# Sheet1.net
KiCad netlist of a schematic drawn in Altium Designer
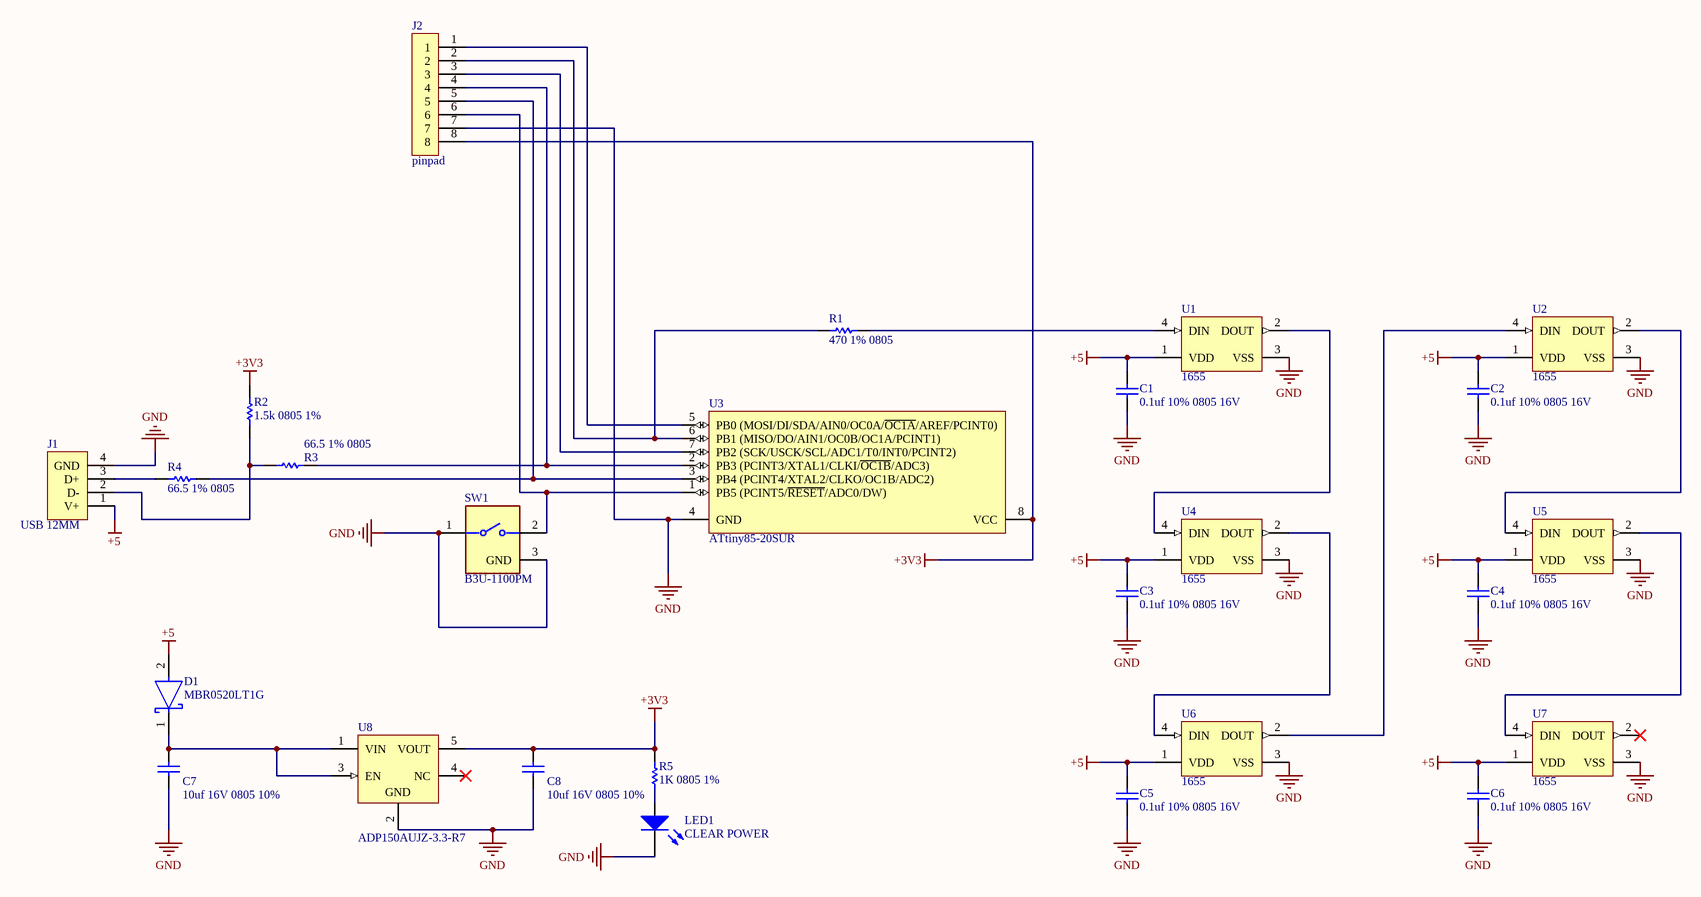
[diagram p0: Sheet1.SchDoc]

(export (version "E")
  (design (tool "Eeschema 10.0.6"))
  (components
    (comp (ref "C1")
      (value "0.1uf 10% 0805 16V")
      (footprint "CAPC2013X140X50NL20T25")
      (fields
        (field (name "PART NUMBER") "08055C104K4Z2A")
        (field (name "MANUFACTURER") "AVX Interconnect / Elco")
      )
      (libsource (lib "Altium Content Vault") (part "CAP"))
    )
    (comp (ref "C2")
      (value "0.1uf 10% 0805 16V")
      (footprint "CAPC2013X140X50NL20T25")
      (fields
        (field (name "PART NUMBER") "08055C104K4Z2A")
        (field (name "MANUFACTURER") "AVX Interconnect / Elco")
      )
      (libsource (lib "Altium Content Vault") (part "CAP"))
    )
    (comp (ref "C3")
      (value "0.1uf 10% 0805 16V")
      (footprint "CAPC2013X140X50NL20T25")
      (fields
        (field (name "PART NUMBER") "08055C104K4Z2A")
        (field (name "MANUFACTURER") "AVX Interconnect / Elco")
      )
      (libsource (lib "Altium Content Vault") (part "CAP"))
    )
    (comp (ref "C4")
      (value "0.1uf 10% 0805 16V")
      (footprint "CAPC2013X140X50NL20T25")
      (fields
        (field (name "PART NUMBER") "08055C104K4Z2A")
        (field (name "MANUFACTURER") "AVX Interconnect / Elco")
      )
      (libsource (lib "Altium Content Vault") (part "CAP"))
    )
    (comp (ref "C5")
      (value "0.1uf 10% 0805 16V")
      (footprint "CAPC2013X140X50NL20T25")
      (fields
        (field (name "PART NUMBER") "08055C104K4Z2A")
        (field (name "MANUFACTURER") "AVX Interconnect / Elco")
      )
      (libsource (lib "Altium Content Vault") (part "CAP"))
    )
    (comp (ref "C6")
      (value "0.1uf 10% 0805 16V")
      (footprint "CAPC2013X140X50NL20T25")
      (fields
        (field (name "PART NUMBER") "08055C104K4Z2A")
        (field (name "MANUFACTURER") "AVX Interconnect / Elco")
      )
      (libsource (lib "Altium Content Vault") (part "CAP"))
    )
    (comp (ref "C7")
      (value "10uf 16V 0805 10%")
      (footprint "CAPC2013X145X50LL20T25")
      (fields (field (name "MANUFACTURER") "Kemet") (field (name "PART NUMBER") "C0805C105K4PACTU"))
      (libsource (lib "Altium Content Vault") (part "CAP"))
    )
    (comp (ref "C8")
      (value "10uf 16V 0805 10%")
      (footprint "CAPC2013X145X50LL20T25")
      (fields (field (name "MANUFACTURER") "Kemet") (field (name "PART NUMBER") "C0805C105K4PACTU"))
      (libsource (lib "Altium Content Vault") (part "CAP"))
    )
    (comp (ref "D1")
      (value "MBR0520LT1G")
      (footprint "FP-425-04-IPC_C")
      (description "DIODE SCHOTTKY 20V 500MA SOD123")
      (libsource (lib "Altium Content Vault") (part "1d6ec82d83fb6aee721767c19dac4b9"))
    )
    (comp (ref "J1") (value "USB 12MM") (footprint "USB A") (libsource (lib "Schlib1") (part "USB")))
    (comp (ref "J2") (value "pinpad") (footprint "open_pad_8") (libsource (lib "Schlib1") (part "pinpad")))
    (comp (ref "LED1")
      (value "CLEAR POWER")
      (footprint "0805_A")
      (description "SMD mono-color Chip LED, WL-SMCW, Bright Green")
      (fields (field (name "PARTNUMBER") "150080VS75000") (field (name "MANUFACTURER") "Wuerth Elektronik"))
      (libsource (lib "Altium Content Vault") (part "WE-LED_K1A2-2"))
    )
    (comp (ref "R1")
      (value "470 1% 0805")
      (footprint "RESC2013X50X30LL20T20")
      (fields (field (name "MANUFACTURER") "Vishay Dale") (field (name "PART NUMBER") "CRCW0805470RFKEA"))
      (libsource (lib "Altium Content Vault") (part "RES"))
    )
    (comp (ref "R2")
      (value "1.5k 0805 1%")
      (footprint "RESC2013X60X35LL10T20")
      (description "RES 1.50K OHM 1/8W 1% 0805 SMD")
      (fields (field (name "MANUFACTURER") "Yageo") (field (name "PARTNUMBER") "RC0805FR-071K5L"))
      (libsource (lib "") (part "RES-2_1"))
    )
    (comp (ref "R3")
      (value "66.5 1% 0805")
      (footprint "RESC2013X50X30NL20T20")
      (fields (field (name "MANUFACTURER") "Vishay Dale") (field (name "PART NUMBER") "CRCW0805680RFKEA"))
      (libsource (lib "Altium Content Vault") (part "RES"))
    )
    (comp (ref "R4")
      (value "66.5 1% 0805")
      (footprint "RESC2013X50X30NL20T20")
      (fields (field (name "MANUFACTURER") "Vishay Dale") (field (name "PART NUMBER") "CRCW0805680RFKEA"))
      (libsource (lib "Altium Content Vault") (part "RES"))
    )
    (comp (ref "R5")
      (value "1K 0805 1%")
      (footprint "RESC2013X60X35ML10T20")
      (description "Chip Resistor, 1 KOhm, +/- 1%, 125 mW, -55 to 155 degC, 0805 (2012 Metric), RoHS, Tape and Reel")
      (fields (field (name "TOLERANCE") "1%") (field (name "MANUFACTURER") "Yageo"))
      (libsource (lib "Altium Content Vault") (part "RES-2"))
    )
    (comp (ref "SW1")
      (value "B3U-1100PM")
      (footprint "FP-B3U-1100PM-MFG")
      (description "SWITCH TACTILE SPST-NO 0.05A 12V")
      (libsource (lib "Altium Content Vault") (part "6d7322ea62e06c21cb959ab9578dfa0"))
    )
    (comp (ref "U1")
      (value "1655")
      (footprint "ADA-RGB-1655_V")
      (fields (field (name "MANUFACTURER") "Adafruit-Industries-LLC"))
      (libsource (lib "Altium Content Vault") (part "ADA-RGB-1655-4"))
    )
    (comp (ref "U2")
      (value "1655")
      (footprint "ADA-RGB-1655_V")
      (fields (field (name "MANUFACTURER") "Adafruit-Industries-LLC"))
      (libsource (lib "Altium Content Vault") (part "ADA-RGB-1655-4"))
    )
    (comp (ref "U3")
      (value "ATtiny85-20SUR")
      (footprint "8S2_L")
      (libsource (lib "Altium Content Vault") (part "MC-8B-ATT25-IL8"))
    )
    (comp (ref "U4")
      (value "1655")
      (footprint "ADA-RGB-1655_V")
      (fields (field (name "MANUFACTURER") "Adafruit-Industries-LLC"))
      (libsource (lib "Altium Content Vault") (part "ADA-RGB-1655-4"))
    )
    (comp (ref "U5")
      (value "1655")
      (footprint "ADA-RGB-1655_V")
      (fields (field (name "MANUFACTURER") "Adafruit-Industries-LLC"))
      (libsource (lib "Altium Content Vault") (part "ADA-RGB-1655-4"))
    )
    (comp (ref "U6")
      (value "1655")
      (footprint "ADA-RGB-1655_V")
      (fields (field (name "MANUFACTURER") "Adafruit-Industries-LLC"))
      (libsource (lib "Altium Content Vault") (part "ADA-RGB-1655-4"))
    )
    (comp (ref "U7")
      (value "1655")
      (footprint "ADA-RGB-1655_V")
      (fields (field (name "MANUFACTURER") "Adafruit-Industries-LLC"))
      (libsource (lib "Altium Content Vault") (part "ADA-RGB-1655-4"))
    )
    (comp (ref "U8")
      (value "ADP150AUJZ-3.3-R7")
      (footprint "ADI-UJ-5_M")
      (fields (field (name "MANUFACTURER") "Analog Devices"))
      (libsource (lib "Altium Content Vault") (part "ADI-ADP1XX-UJ-5"))
    )
  )
  (nets
    (net (code "1") (name "+3V3") (class "Default")
      (node (ref "C8") (pin "2") (pinfunction "2_2") (pintype "passive"))
      (node (ref "J2") (pin "8") (pinfunction "8_8") (pintype "passive"))
      (node (ref "R2") (pin "2") (pinfunction "2_2") (pintype "passive"))
      (node (ref "R5") (pin "1") (pinfunction "1_1") (pintype "passive"))
      (node (ref "U3") (pin "8") (pinfunction "VCC_8") (pintype "power_in"))
      (node (ref "U8") (pin "5") (pinfunction "VOUT_5") (pintype "power_in"))
    )
    (net (code "2") (name "+5") (class "Default")
      (node (ref "C1") (pin "2") (pinfunction "2_2") (pintype "passive"))
      (node (ref "C2") (pin "2") (pinfunction "2_2") (pintype "passive"))
      (node (ref "C3") (pin "2") (pinfunction "2_2") (pintype "passive"))
      (node (ref "C4") (pin "2") (pinfunction "2_2") (pintype "passive"))
      (node (ref "C5") (pin "2") (pinfunction "2_2") (pintype "passive"))
      (node (ref "C6") (pin "2") (pinfunction "2_2") (pintype "passive"))
      (node (ref "D1") (pin "2") (pinfunction "A_2") (pintype "passive"))
      (node (ref "J1") (pin "1") (pinfunction "V+_1") (pintype "passive"))
      (node (ref "U1") (pin "1") (pinfunction "VDD_1") (pintype "power_in"))
      (node (ref "U2") (pin "1") (pinfunction "VDD_1") (pintype "power_in"))
      (node (ref "U4") (pin "1") (pinfunction "VDD_1") (pintype "power_in"))
      (node (ref "U5") (pin "1") (pinfunction "VDD_1") (pintype "power_in"))
      (node (ref "U6") (pin "1") (pinfunction "VDD_1") (pintype "power_in"))
      (node (ref "U7") (pin "1") (pinfunction "VDD_1") (pintype "power_in"))
    )
    (net (code "3") (name "GND") (class "Default")
      (node (ref "C1") (pin "1") (pinfunction "1_1") (pintype "passive"))
      (node (ref "C2") (pin "1") (pinfunction "1_1") (pintype "passive"))
      (node (ref "C3") (pin "1") (pinfunction "1_1") (pintype "passive"))
      (node (ref "C4") (pin "1") (pinfunction "1_1") (pintype "passive"))
      (node (ref "C5") (pin "1") (pinfunction "1_1") (pintype "passive"))
      (node (ref "C6") (pin "1") (pinfunction "1_1") (pintype "passive"))
      (node (ref "C7") (pin "1") (pinfunction "1_1") (pintype "passive"))
      (node (ref "C8") (pin "1") (pinfunction "1_1") (pintype "passive"))
      (node (ref "J1") (pin "4") (pinfunction "GND_4") (pintype "passive"))
      (node (ref "J2") (pin "7") (pinfunction "7_7") (pintype "passive"))
      (node (ref "LED1") (pin "1") (pinfunction "K_1") (pintype "passive"))
      (node (ref "SW1") (pin "1") (pinfunction "1_1") (pintype "passive"))
      (node (ref "SW1") (pin "3") (pinfunction "GND_3") (pintype "power_in"))
      (node (ref "U1") (pin "3") (pinfunction "VSS_3") (pintype "power_in"))
      (node (ref "U2") (pin "3") (pinfunction "VSS_3") (pintype "power_in"))
      (node (ref "U3") (pin "4") (pinfunction "GND_4") (pintype "power_in"))
      (node (ref "U4") (pin "3") (pinfunction "VSS_3") (pintype "power_in"))
      (node (ref "U5") (pin "3") (pinfunction "VSS_3") (pintype "power_in"))
      (node (ref "U6") (pin "3") (pinfunction "VSS_3") (pintype "power_in"))
      (node (ref "U7") (pin "3") (pinfunction "VSS_3") (pintype "power_in"))
      (node (ref "U8") (pin "2") (pinfunction "GND_2") (pintype "power_in"))
    )
    (net (code "4") (name "Net-(D1-C)") (class "Default")
      (node (ref "C7") (pin "2") (pinfunction "2_2") (pintype "passive"))
      (node (ref "D1") (pin "1") (pinfunction "C_1") (pintype "passive"))
      (node (ref "U8") (pin "1") (pinfunction "VIN_1") (pintype "power_in"))
      (node (ref "U8") (pin "3") (pinfunction "EN_3") (pintype "input"))
    )
    (net (code "5") (name "Net-(J1-D+)") (class "Default")
      (node (ref "J1") (pin "3") (pinfunction "D+_3") (pintype "passive"))
      (node (ref "R4") (pin "1") (pinfunction "1_1") (pintype "passive"))
    )
    (net (code "6") (name "Net-(J1-D-)") (class "Default")
      (node (ref "J1") (pin "2") (pinfunction "D-_2") (pintype "passive"))
      (node (ref "R2") (pin "1") (pinfunction "1_1") (pintype "passive"))
      (node (ref "R3") (pin "1") (pinfunction "1_1") (pintype "passive"))
    )
    (net (code "7") (name "Net-(LED1-A)") (class "Default")
      (node (ref "LED1") (pin "2") (pinfunction "A_2") (pintype "passive"))
      (node (ref "R5") (pin "2") (pinfunction "2_2") (pintype "passive"))
    )
    (net (code "8") (name "Net-(U1-DIN)") (class "Default")
      (node (ref "R1") (pin "2") (pinfunction "2_2") (pintype "passive"))
      (node (ref "U1") (pin "4") (pinfunction "DIN_4") (pintype "input"))
    )
    (net (code "9") (name "Net-(U1-DOUT)") (class "Default")
      (node (ref "U1") (pin "2") (pinfunction "DOUT_2") (pintype "output"))
      (node (ref "U4") (pin "4") (pinfunction "DIN_4") (pintype "input"))
    )
    (net (code "10") (name "Net-(U2-DIN)") (class "Default")
      (node (ref "U2") (pin "4") (pinfunction "DIN_4") (pintype "input"))
      (node (ref "U6") (pin "2") (pinfunction "DOUT_2") (pintype "output"))
    )
    (net (code "11") (name "Net-(U2-DOUT)") (class "Default")
      (node (ref "U2") (pin "2") (pinfunction "DOUT_2") (pintype "output"))
      (node (ref "U5") (pin "4") (pinfunction "DIN_4") (pintype "input"))
    )
    (net (code "12") (name "Net-(U3-PB0_(MOSI{slash}DI{slash}SDA{slash}AIN0{slash}OC0A{slash}~{OC1A}{slash}AREF{slash}PCINT0))") (class "Default")
      (node (ref "J2") (pin "1") (pinfunction "1_1") (pintype "passive"))
      (node (ref "U3") (pin "5") (pinfunction "PB0_(MOSI/DI/SDA/AIN0/OC0A/~{OC1A}/AREF/PCINT0)_5") (pintype "bidirectional"))
    )
    (net (code "13") (name "Net-(U3-PB1_(MISO{slash}DO{slash}AIN1{slash}OC0B{slash}OC1A{slash}PCINT1))") (class "Default")
      (node (ref "J2") (pin "2") (pinfunction "2_2") (pintype "passive"))
      (node (ref "R1") (pin "1") (pinfunction "1_1") (pintype "passive"))
      (node (ref "U3") (pin "6") (pinfunction "PB1_(MISO/DO/AIN1/OC0B/OC1A/PCINT1)_6") (pintype "bidirectional"))
    )
    (net (code "14") (name "Net-(U3-PB2_(SCK{slash}USCK{slash}SCL{slash}ADC1{slash}T0{slash}INT0{slash}PCINT2))") (class "Default")
      (node (ref "J2") (pin "3") (pinfunction "3_3") (pintype "passive"))
      (node (ref "U3") (pin "7") (pinfunction "PB2_(SCK/USCK/SCL/ADC1/T0/INT0/PCINT2)_7") (pintype "bidirectional"))
    )
    (net (code "15") (name "Net-(U3-PB3_(PCINT3{slash}XTAL1{slash}CLKI{slash}~{OC1B}{slash}ADC3))") (class "Default")
      (node (ref "J2") (pin "4") (pinfunction "4_4") (pintype "passive"))
      (node (ref "R3") (pin "2") (pinfunction "2_2") (pintype "passive"))
      (node (ref "U3") (pin "2") (pinfunction "PB3_(PCINT3/XTAL1/CLKI/~{OC1B}/ADC3)_2") (pintype "bidirectional"))
    )
    (net (code "16") (name "Net-(U3-PB4_(PCINT4{slash}XTAL2{slash}CLKO{slash}OC1B{slash}ADC2))") (class "Default")
      (node (ref "J2") (pin "5") (pinfunction "5_5") (pintype "passive"))
      (node (ref "R4") (pin "2") (pinfunction "2_2") (pintype "passive"))
      (node (ref "U3") (pin "3") (pinfunction "PB4_(PCINT4/XTAL2/CLKO/OC1B/ADC2)_3") (pintype "bidirectional"))
    )
    (net (code "17") (name "Net-(U3-PB5_(PCINT5{slash}~{RESET}{slash}ADC0{slash}DW))") (class "Default")
      (node (ref "J2") (pin "6") (pinfunction "6_6") (pintype "passive"))
      (node (ref "SW1") (pin "2") (pinfunction "2_2") (pintype "passive"))
      (node (ref "U3") (pin "1") (pinfunction "PB5_(PCINT5/~{RESET}/ADC0/DW)_1") (pintype "bidirectional"))
    )
    (net (code "18") (name "Net-(U4-DOUT)") (class "Default")
      (node (ref "U4") (pin "2") (pinfunction "DOUT_2") (pintype "output"))
      (node (ref "U6") (pin "4") (pinfunction "DIN_4") (pintype "input"))
    )
    (net (code "19") (name "Net-(U5-DOUT)") (class "Default")
      (node (ref "U5") (pin "2") (pinfunction "DOUT_2") (pintype "output"))
      (node (ref "U7") (pin "4") (pinfunction "DIN_4") (pintype "input"))
    )
    (net (code "20") (name "unconnected-(U7-DOUT-Pad2)") (class "Default")
      (node (ref "U7") (pin "2") (pinfunction "DOUT_2") (pintype "output+no_connect"))
    )
    (net (code "21") (name "unconnected-(U8-NC-Pad4)") (class "Default")
      (node (ref "U8") (pin "4") (pinfunction "NC_4") (pintype "passive+no_connect"))
    )
  )
)
